# limiter.net
KiCad netlist of a schematic drawn in Altium Designer
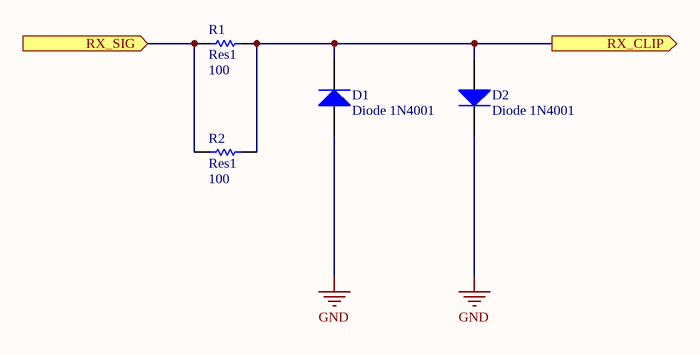
[diagram p0: limiter.SchDoc]

(export (version "E")
  (design (tool "Eeschema 10.0.6"))
  (components
    (comp (ref "D1")
      (value "Diode 1N4001")
      (footprint "DO-41")
      (description "1 Amp General Purpose Rectifier")
      (fields (field (name "PUBLISHER") "Altium Limited"))
      (libsource (lib "Miscellaneous Devices") (part "Diode 1N4001"))
    )
    (comp (ref "D2")
      (value "Diode 1N4001")
      (footprint "DO-41")
      (description "1 Amp General Purpose Rectifier")
      (fields (field (name "PUBLISHER") "Altium Limited"))
      (libsource (lib "Miscellaneous Devices") (part "Diode 1N4001"))
    )
    (comp (ref "R1")
      (value "Res1")
      (footprint "AXIAL-0.1-RES")
      (description "Resistor")
      (fields
        (field (name "ALTIUM_VALUE") "100")
        (field (name "MANUFACTURER PART NUMBER") "CFR-25JB-52-100R")
        (field (name "TOLERANCE") "0.05")
        (field (name "PUBLISHER") "Altium Limited")
      )
      (libsource (lib "ECE295-Resistors-TH") (part "RES 100 OHM 5% 1/4W AXIAL"))
    )
    (comp (ref "R2")
      (value "Res1")
      (footprint "AXIAL-0.1-RES")
      (description "Resistor")
      (fields
        (field (name "ALTIUM_VALUE") "100")
        (field (name "MANUFACTURER PART NUMBER") "CFR-25JB-52-100R")
        (field (name "TOLERANCE") "0.05")
        (field (name "PUBLISHER") "Altium Limited")
      )
      (libsource (lib "ECE295-Resistors-TH") (part "RES 100 OHM 5% 1/4W AXIAL"))
    )
  )
  (nets
    (net (code "1") (name "/RX_CLIP") (class "Default")
      (node (ref "D1") (pin "2") (pinfunction "K_2") (pintype "passive"))
      (node (ref "D2") (pin "1") (pinfunction "A_1") (pintype "passive"))
      (node (ref "R1") (pin "2") (pinfunction "2_2") (pintype "passive"))
      (node (ref "R2") (pin "2") (pinfunction "2_2") (pintype "passive"))
    )
    (net (code "2") (name "/RX_SIG") (class "Default")
      (node (ref "R1") (pin "1") (pinfunction "1_1") (pintype "passive"))
      (node (ref "R2") (pin "1") (pinfunction "1_1") (pintype "passive"))
    )
    (net (code "3") (name "GND") (class "Default")
      (node (ref "D1") (pin "1") (pinfunction "A_1") (pintype "passive"))
      (node (ref "D2") (pin "2") (pinfunction "K_2") (pintype "passive"))
    )
  )
)
